# RelayNode.net
KiCad netlist of a schematic drawn in Altium Designer
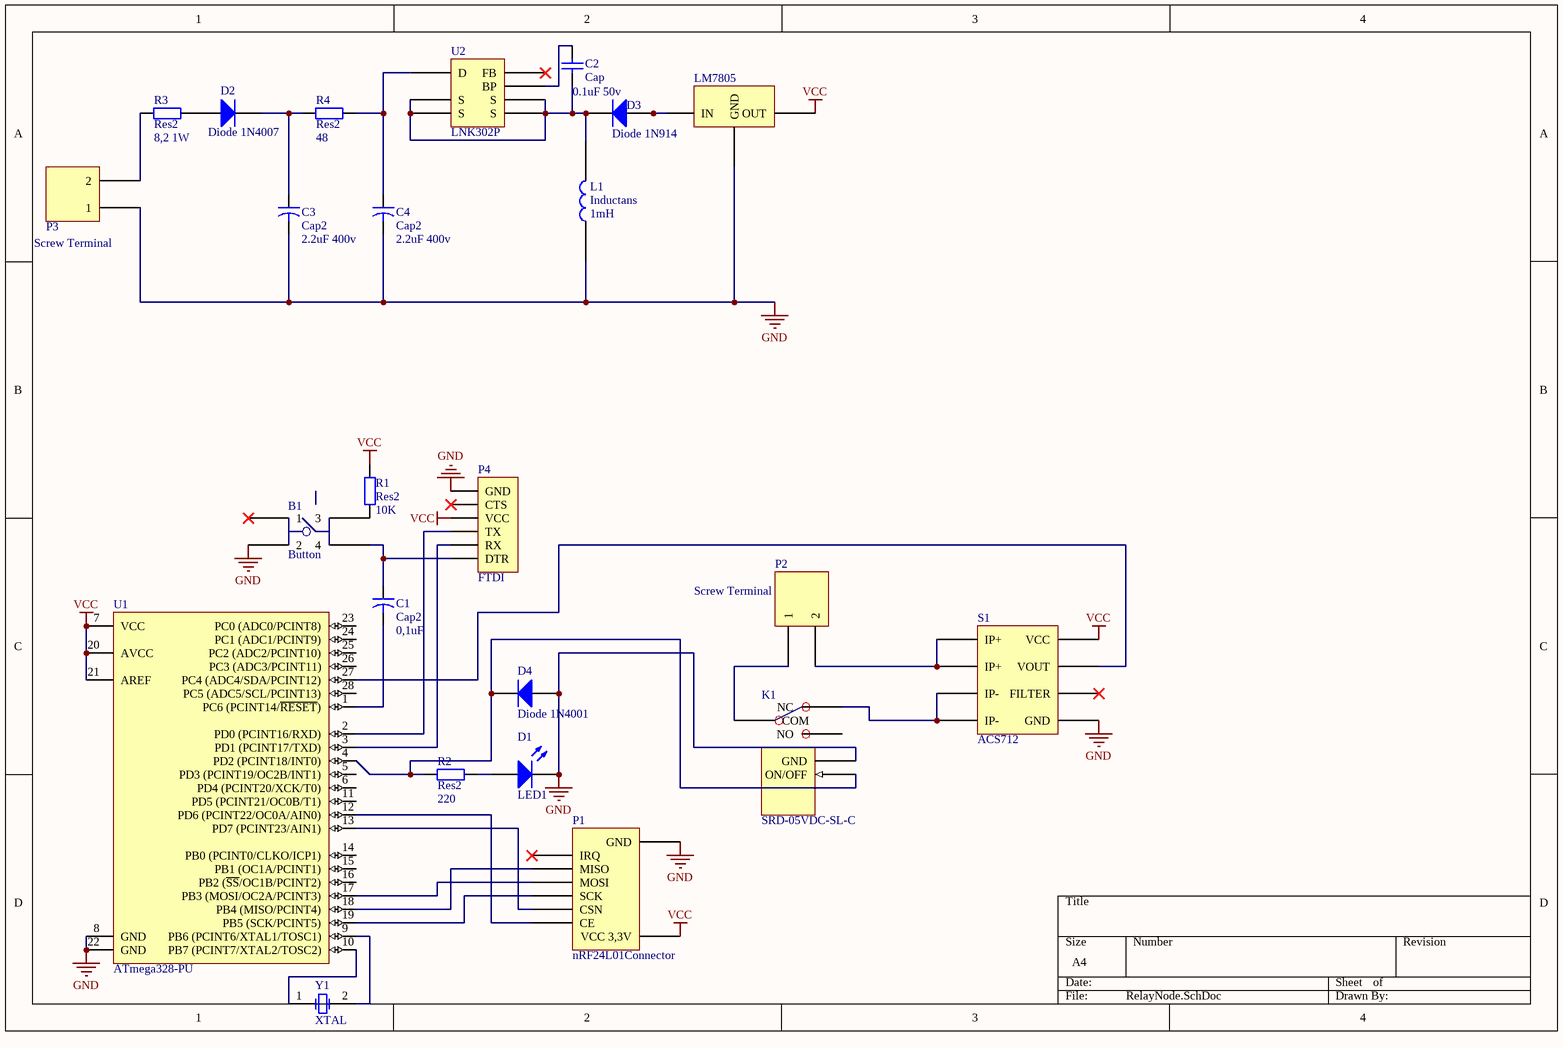
[diagram p0: RelayNode.SchDoc]

(export (version "E")
  (design (tool "Eeschema 10.0.6"))
  (components
    (comp (ref "B1") (value "Button") (footprint "Button") (libsource (lib "Button") (part "Button")))
    (comp (ref "C1")
      (value "Cap2")
      (footprint "CAPR5-4X5")
      (description "Capacitor")
      (fields (field (name "ALTIUM_VALUE") "0,1uF") (field (name "PUBLISHER") "Altium Limited"))
      (libsource (lib "Miscellaneous Devices") (part "Cap2"))
    )
    (comp (ref "C2")
      (value "Cap")
      (footprint "RAD-0.3")
      (description "Capacitor")
      (fields (field (name "ALTIUM_VALUE") "0.1uF 50v") (field (name "PUBLISHER") "Altium Limited"))
      (libsource (lib "Miscellaneous Devices") (part "Cap"))
    )
    (comp (ref "C3")
      (value "Cap2")
      (footprint "CAPR5-4X5")
      (description "Capacitor")
      (fields (field (name "ALTIUM_VALUE") "2.2uF 400v") (field (name "PUBLISHER") "Altium Limited"))
      (libsource (lib "Miscellaneous Devices") (part "Cap2"))
    )
    (comp (ref "C4")
      (value "Cap2")
      (footprint "CAPR5-4X5")
      (description "Capacitor")
      (fields (field (name "ALTIUM_VALUE") "2.2uF 400v") (field (name "PUBLISHER") "Altium Limited"))
      (libsource (lib "Miscellaneous Devices") (part "Cap2"))
    )
    (comp (ref "D1")
      (value "LED1")
      (footprint "LED-1")
      (description "Typical RED GaAs LED")
      (fields (field (name "PUBLISHER") "Altium Limited"))
      (libsource (lib "Miscellaneous Devices") (part "LED1"))
    )
    (comp (ref "D2")
      (value "Diode 1N4007")
      (footprint "DO-41")
      (description "1 Amp General Purpose Rectifier")
      (fields (field (name "PUBLISHER") "Altium Limited"))
      (libsource (lib "Miscellaneous Devices") (part "Diode 1N4007"))
    )
    (comp (ref "D3")
      (value "Diode 1N914")
      (footprint "DO-35")
      (description "High Conductance Fast Diode")
      (fields (field (name "PUBLISHER") "Altium Limited"))
      (libsource (lib "Miscellaneous Devices") (part "Diode 1N914"))
    )
    (comp (ref "D4")
      (value "Diode 1N4001")
      (footprint "DO-41")
      (description "1 Amp General Purpose Rectifier")
      (fields (field (name "PUBLISHER") "Altium Limited"))
      (libsource (lib "Miscellaneous Devices") (part "Diode 1N4001"))
    )
    (comp (ref "K1")
      (value "SRD-05VDC-SL-C")
      (footprint "SRD-05VDC-SL-C")
      (libsource (lib "SRD-05VDC-SL-c") (part "SRD-05VDC-SL-C"))
    )
    (comp (ref "L1")
      (value "Inductans")
      (footprint "Axial 0.8")
      (fields (field (name "ALTIUM_VALUE") "1mH"))
      (libsource (lib "Axial 0.8 Induc") (part "Inductans"))
    )
    (comp (ref "LM7805") (value "~") (footprint "TO-220-AB") (libsource (lib "LM7805") (part "LM7805")))
    (comp (ref "P1")
      (value "nRF24L01Connector")
      (footprint "HDR2X4")
      (libsource (lib "nRF24L01Connector") (part "nRF24L01Connector"))
    )
    (comp (ref "P2")
      (value "Screw Terminal")
      (footprint "PCBComponent_1")
      (description "Screw Terminal Block Connector 2 Pins")
      (libsource (lib "Screw Terminal 2P") (part "Screw Terminal"))
    )
    (comp (ref "P3")
      (value "Screw Terminal")
      (footprint "PCBComponent_1")
      (description "Screw Terminal Block Connector 2 Pins")
      (libsource (lib "") (part "Screw Terminal_1"))
    )
    (comp (ref "P4")
      (value "FTDI")
      (footprint "HDR1X6")
      (description "Header, 6-Pin")
      (fields (field (name "PUBLISHER") "Altium Limited"))
      (libsource (lib "Miscellaneous Connectors") (part "Header 6"))
    )
    (comp (ref "R1")
      (value "Res2")
      (footprint "AXIAL-0.4")
      (description "Resistor")
      (fields (field (name "ALTIUM_VALUE") "10K") (field (name "PUBLISHER") "Altium Limited"))
      (libsource (lib "") (part "Res2_1"))
    )
    (comp (ref "R2")
      (value "Res2")
      (footprint "AXIAL-0.4")
      (description "Resistor")
      (fields (field (name "ALTIUM_VALUE") "220") (field (name "PUBLISHER") "Altium Limited"))
      (libsource (lib "Miscellaneous Devices") (part "Res2"))
    )
    (comp (ref "R3")
      (value "Res2")
      (footprint "Axial 1.0")
      (description "Resistor")
      (fields (field (name "ALTIUM_VALUE") "8,2 1W") (field (name "PUBLISHER") "Altium Limited"))
      (libsource (lib "Miscellaneous Devices") (part "Res2"))
    )
    (comp (ref "R4")
      (value "Res2")
      (footprint "AXIAL-0.4")
      (description "Resistor")
      (fields (field (name "ALTIUM_VALUE") "48") (field (name "PUBLISHER") "Altium Limited"))
      (libsource (lib "Miscellaneous Devices") (part "Res2"))
    )
    (comp (ref "S1")
      (value "ACS712")
      (footprint "SOIC127P600X175-8N")
      (libsource (lib "ACS712") (part "ACS712"))
    )
    (comp (ref "U1")
      (value "ATmega328-PU")
      (footprint "28P3")
      (fields (field (name "PUBLISHER") "Altium Limited"))
      (libsource (lib "Atmel Microcontroller 8-Bit megaAVR") (part "ATmega328-PU"))
    )
    (comp (ref "U2")
      (value "LNK302P")
      (footprint "LNK302 - duplicate")
      (description "LNK302P DIP")
      (libsource (lib "LNK302P") (part "LNK302P"))
    )
    (comp (ref "Y1")
      (value "XTAL")
      (footprint "R38")
      (description "Crystal Oscillator")
      (fields (field (name "PUBLISHER") "Altium Limited"))
      (libsource (lib "Miscellaneous Devices") (part "XTAL"))
    )
  )
  (nets
    (net (code "1") (name "GND") (class "Default")
      (node (ref "B1") (pin "2") (pinfunction "2_2") (pintype "passive"))
      (node (ref "C3") (pin "2") (pinfunction "2_2") (pintype "passive"))
      (node (ref "C4") (pin "2") (pinfunction "2_2") (pintype "passive"))
      (node (ref "D1") (pin "2") (pinfunction "K_2") (pintype "passive"))
      (node (ref "D4") (pin "1") (pinfunction "A_1") (pintype "passive"))
      (node (ref "K1") (pin "4") (pinfunction "GND_4") (pintype "passive"))
      (node (ref "L1") (pin "2") (pinfunction "2_2") (pintype "passive"))
      (node (ref "LM7805") (pin "2") (pinfunction "GND_2") (pintype "passive"))
      (node (ref "P1") (pin "2") (pinfunction "GND_2") (pintype "passive"))
      (node (ref "P3") (pin "1") (pinfunction "1_1") (pintype "passive"))
      (node (ref "P4") (pin "1") (pinfunction "GND_1") (pintype "passive"))
      (node (ref "S1") (pin "5") (pinfunction "GND_5") (pintype "passive"))
      (node (ref "U1") (pin "22") (pinfunction "GND_22") (pintype "power_in"))
      (node (ref "U1") (pin "8") (pinfunction "GND_8") (pintype "power_in"))
    )
    (net (code "2") (name "Net-(B1-Pad3)") (class "Default")
      (node (ref "B1") (pin "3") (pinfunction "3_3") (pintype "passive"))
      (node (ref "R1") (pin "1") (pinfunction "1_1") (pintype "passive"))
    )
    (net (code "3") (name "Net-(D1-A)") (class "Default")
      (node (ref "D1") (pin "1") (pinfunction "A_1") (pintype "passive"))
      (node (ref "R2") (pin "2") (pinfunction "2_2") (pintype "passive"))
    )
    (net (code "4") (name "Net-(D2-A)") (class "Default")
      (node (ref "D2") (pin "1") (pinfunction "A_1") (pintype "passive"))
      (node (ref "R3") (pin "2") (pinfunction "2_2") (pintype "passive"))
    )
    (net (code "5") (name "Net-(D2-K)") (class "Default")
      (node (ref "C3") (pin "1") (pinfunction "1_1") (pintype "passive"))
      (node (ref "D2") (pin "2") (pinfunction "K_2") (pintype "passive"))
      (node (ref "R4") (pin "1") (pinfunction "1_1") (pintype "passive"))
    )
    (net (code "6") (name "Net-(D3-A)") (class "Default")
      (node (ref "D3") (pin "1") (pinfunction "A_1") (pintype "passive"))
      (node (ref "LM7805") (pin "1") (pinfunction "IN_1") (pintype "passive"))
    )
    (net (code "7") (name "Net-(D3-K)") (class "Default")
      (node (ref "C2") (pin "1") (pinfunction "1_1") (pintype "passive"))
      (node (ref "D3") (pin "2") (pinfunction "K_2") (pintype "passive"))
      (node (ref "L1") (pin "1") (pinfunction "1_1") (pintype "passive"))
      (node (ref "U2") (pin "1") (pinfunction "S_1") (pintype "passive"))
      (node (ref "U2") (pin "2") (pinfunction "S_2") (pintype "passive"))
      (node (ref "U2") (pin "7") (pinfunction "S_7") (pintype "passive"))
      (node (ref "U2") (pin "8") (pinfunction "S_8") (pintype "passive"))
    )
    (net (code "8") (name "Net-(D4-K)") (class "Default")
      (node (ref "D4") (pin "2") (pinfunction "K_2") (pintype "passive"))
      (node (ref "K1") (pin "5") (pinfunction "ON/OFF_5") (pintype "input"))
      (node (ref "R2") (pin "1") (pinfunction "1_1") (pintype "passive"))
      (node (ref "U1") (pin "4") (pinfunction "PD2_(PCINT18/INT0)_4") (pintype "bidirectional"))
    )
    (net (code "9") (name "Net-(K1-COM)") (class "Default")
      (node (ref "K1") (pin "1") (pinfunction "COM_1") (pintype "passive"))
      (node (ref "P2") (pin "1") (pinfunction "1_1") (pintype "passive"))
    )
    (net (code "10") (name "Net-(K1-NC)") (class "Default")
      (node (ref "K1") (pin "2") (pinfunction "NC_2") (pintype "passive"))
      (node (ref "S1") (pin "3") (pinfunction "IP-_3") (pintype "passive"))
    )
    (net (code "11") (name "Net-(P1-CE)") (class "Default")
      (node (ref "P1") (pin "3") (pinfunction "CE_3") (pintype "passive"))
      (node (ref "U1") (pin "12") (pinfunction "PD6_(PCINT22/OC0A/AIN0)_12") (pintype "bidirectional"))
    )
    (net (code "12") (name "Net-(P1-CSN)") (class "Default")
      (node (ref "P1") (pin "4") (pinfunction "CSN_4") (pintype "passive"))
      (node (ref "U1") (pin "13") (pinfunction "PD7_(PCINT23/AIN1)_13") (pintype "bidirectional"))
    )
    (net (code "13") (name "Net-(P1-MISO)") (class "Default")
      (node (ref "P1") (pin "7") (pinfunction "MISO_7") (pintype "passive"))
      (node (ref "U1") (pin "18") (pinfunction "PB4_(MISO/PCINT4)_18") (pintype "bidirectional"))
    )
    (net (code "14") (name "Net-(P1-MOSI)") (class "Default")
      (node (ref "P1") (pin "6") (pinfunction "MOSI_6") (pintype "passive"))
      (node (ref "U1") (pin "17") (pinfunction "PB3_(MOSI/OC2A/PCINT3)_17") (pintype "bidirectional"))
    )
    (net (code "15") (name "Net-(P1-SCK)") (class "Default")
      (node (ref "P1") (pin "5") (pinfunction "SCK_5") (pintype "passive"))
      (node (ref "U1") (pin "19") (pinfunction "PB5_(SCK/PCINT5)_19") (pintype "bidirectional"))
    )
    (net (code "16") (name "Net-(P3-Pad2)") (class "Default")
      (node (ref "P3") (pin "2") (pinfunction "2_2") (pintype "passive"))
      (node (ref "R3") (pin "1") (pinfunction "1_1") (pintype "passive"))
    )
    (net (code "17") (name "Net-(P4-DTR)") (class "Default")
      (node (ref "B1") (pin "4") (pinfunction "4_4") (pintype "passive"))
      (node (ref "C1") (pin "1") (pinfunction "1_1") (pintype "passive"))
      (node (ref "P4") (pin "6") (pinfunction "DTR_6") (pintype "passive"))
    )
    (net (code "18") (name "Net-(P4-RX)") (class "Default")
      (node (ref "P4") (pin "5") (pinfunction "RX_5") (pintype "passive"))
      (node (ref "U1") (pin "3") (pinfunction "PD1_(PCINT17/TXD)_3") (pintype "bidirectional"))
    )
    (net (code "19") (name "Net-(P4-TX)") (class "Default")
      (node (ref "P4") (pin "4") (pinfunction "TX_4") (pintype "passive"))
      (node (ref "U1") (pin "2") (pinfunction "PD0_(PCINT16/RXD)_2") (pintype "bidirectional"))
    )
    (net (code "20") (name "Net-(S1-IP+)") (class "Default")
      (node (ref "P2") (pin "2") (pinfunction "2_2") (pintype "passive"))
      (node (ref "S1") (pin "1") (pinfunction "IP+_1") (pintype "passive"))
    )
    (net (code "21") (name "Net-(S1-VOUT)") (class "Default")
      (node (ref "S1") (pin "7") (pinfunction "VOUT_7") (pintype "passive"))
      (node (ref "U1") (pin "27") (pinfunction "PC4_(ADC4/SDA/PCINT12)_27") (pintype "bidirectional"))
    )
    (net (code "22") (name "Net-(U1-PB6_(PCINT6{slash}XTAL1{slash}TOSC1))") (class "Default")
      (node (ref "U1") (pin "9") (pinfunction "PB6_(PCINT6/XTAL1/TOSC1)_9") (pintype "bidirectional"))
      (node (ref "Y1") (pin "2") (pinfunction "OSC2_2") (pintype "passive"))
    )
    (net (code "23") (name "Net-(U1-PB7_(PCINT7{slash}XTAL2{slash}TOSC2))") (class "Default")
      (node (ref "U1") (pin "10") (pinfunction "PB7_(PCINT7/XTAL2/TOSC2)_10") (pintype "bidirectional"))
      (node (ref "Y1") (pin "1") (pinfunction "OSC1_1") (pintype "passive"))
    )
    (net (code "24") (name "Net-(U1-PC6_(PCINT14{slash}~{RESET}))") (class "Default")
      (node (ref "C1") (pin "2") (pinfunction "2_2") (pintype "passive"))
      (node (ref "U1") (pin "1") (pinfunction "PC6_(PCINT14/~{RESET})_1") (pintype "bidirectional"))
    )
    (net (code "25") (name "Net-(U2-BP)") (class "Default")
      (node (ref "C2") (pin "2") (pinfunction "2_2") (pintype "passive"))
      (node (ref "U2") (pin "3") (pinfunction "BP_3") (pintype "passive"))
    )
    (net (code "26") (name "Net-(U2-D)") (class "Default")
      (node (ref "C4") (pin "1") (pinfunction "1_1") (pintype "passive"))
      (node (ref "R4") (pin "2") (pinfunction "2_2") (pintype "passive"))
      (node (ref "U2") (pin "5") (pinfunction "D_5") (pintype "passive"))
    )
    (net (code "27") (name "VCC") (class "Default")
      (node (ref "LM7805") (pin "3") (pinfunction "OUT_3") (pintype "passive"))
      (node (ref "P1") (pin "1") (pinfunction "VCC_3,3V_1") (pintype "passive"))
      (node (ref "P4") (pin "3") (pinfunction "VCC_3") (pintype "passive"))
      (node (ref "R1") (pin "2") (pinfunction "2_2") (pintype "passive"))
      (node (ref "S1") (pin "8") (pinfunction "VCC_8") (pintype "passive"))
      (node (ref "U1") (pin "20") (pinfunction "AVCC_20") (pintype "power_in"))
      (node (ref "U1") (pin "21") (pinfunction "AREF_21") (pintype "power_in"))
      (node (ref "U1") (pin "7") (pinfunction "VCC_7") (pintype "power_in"))
    )
    (net (code "28") (name "unconnected-(B1-Pad1)") (class "Default")
      (node (ref "B1") (pin "1") (pinfunction "1_1") (pintype "passive+no_connect"))
    )
    (net (code "29") (name "unconnected-(K1-NO-Pad3)") (class "Default")
      (node (ref "K1") (pin "3") (pinfunction "NO_3") (pintype "passive"))
    )
    (net (code "30") (name "unconnected-(P1-IRQ-Pad8)") (class "Default")
      (node (ref "P1") (pin "8") (pinfunction "IRQ_8") (pintype "passive+no_connect"))
    )
    (net (code "31") (name "unconnected-(P4-CTS-Pad2)") (class "Default")
      (node (ref "P4") (pin "2") (pinfunction "CTS_2") (pintype "passive+no_connect"))
    )
    (net (code "32") (name "unconnected-(S1-FILTER-Pad6)") (class "Default")
      (node (ref "S1") (pin "6") (pinfunction "FILTER_6") (pintype "passive+no_connect"))
    )
    (net (code "33") (name "unconnected-(U1-PB0_(PCINT0{slash}CLKO{slash}ICP1)-Pad14)") (class "Default")
      (node (ref "U1") (pin "14") (pinfunction "PB0_(PCINT0/CLKO/ICP1)_14") (pintype "bidirectional"))
    )
    (net (code "34") (name "unconnected-(U1-PB1_(OC1A{slash}PCINT1)-Pad15)") (class "Default")
      (node (ref "U1") (pin "15") (pinfunction "PB1_(OC1A/PCINT1)_15") (pintype "bidirectional"))
    )
    (net (code "35") (name "unconnected-(U1-PB2_(~{SS}{slash}OC1B{slash}PCINT2)-Pad16)") (class "Default")
      (node (ref "U1") (pin "16") (pinfunction "PB2_(~{SS}/OC1B/PCINT2)_16") (pintype "bidirectional"))
    )
    (net (code "36") (name "unconnected-(U1-PC0_(ADC0{slash}PCINT8)-Pad23)") (class "Default")
      (node (ref "U1") (pin "23") (pinfunction "PC0_(ADC0/PCINT8)_23") (pintype "bidirectional"))
    )
    (net (code "37") (name "unconnected-(U1-PC1_(ADC1{slash}PCINT9)-Pad24)") (class "Default")
      (node (ref "U1") (pin "24") (pinfunction "PC1_(ADC1/PCINT9)_24") (pintype "bidirectional"))
    )
    (net (code "38") (name "unconnected-(U1-PC2_(ADC2{slash}PCINT10)-Pad25)") (class "Default")
      (node (ref "U1") (pin "25") (pinfunction "PC2_(ADC2/PCINT10)_25") (pintype "bidirectional"))
    )
    (net (code "39") (name "unconnected-(U1-PC3_(ADC3{slash}PCINT11)-Pad26)") (class "Default")
      (node (ref "U1") (pin "26") (pinfunction "PC3_(ADC3/PCINT11)_26") (pintype "bidirectional"))
    )
    (net (code "40") (name "unconnected-(U1-PC5_(ADC5{slash}SCL{slash}PCINT13)-Pad28)") (class "Default")
      (node (ref "U1") (pin "28") (pinfunction "PC5_(ADC5/SCL/PCINT13)_28") (pintype "bidirectional"))
    )
    (net (code "41") (name "unconnected-(U1-PD3_(PCINT19{slash}OC2B{slash}INT1)-Pad5)") (class "Default")
      (node (ref "U1") (pin "5") (pinfunction "PD3_(PCINT19/OC2B/INT1)_5") (pintype "bidirectional"))
    )
    (net (code "42") (name "unconnected-(U1-PD4_(PCINT20{slash}XCK{slash}T0)-Pad6)") (class "Default")
      (node (ref "U1") (pin "6") (pinfunction "PD4_(PCINT20/XCK/T0)_6") (pintype "bidirectional"))
    )
    (net (code "43") (name "unconnected-(U1-PD5_(PCINT21{slash}OC0B{slash}T1)-Pad11)") (class "Default")
      (node (ref "U1") (pin "11") (pinfunction "PD5_(PCINT21/OC0B/T1)_11") (pintype "bidirectional"))
    )
    (net (code "44") (name "unconnected-(U2-FB-Pad4)") (class "Default")
      (node (ref "U2") (pin "4") (pinfunction "FB_4") (pintype "passive+no_connect"))
    )
  )
)
